# sensors.net
KiCad netlist of a schematic drawn in Altium Designer
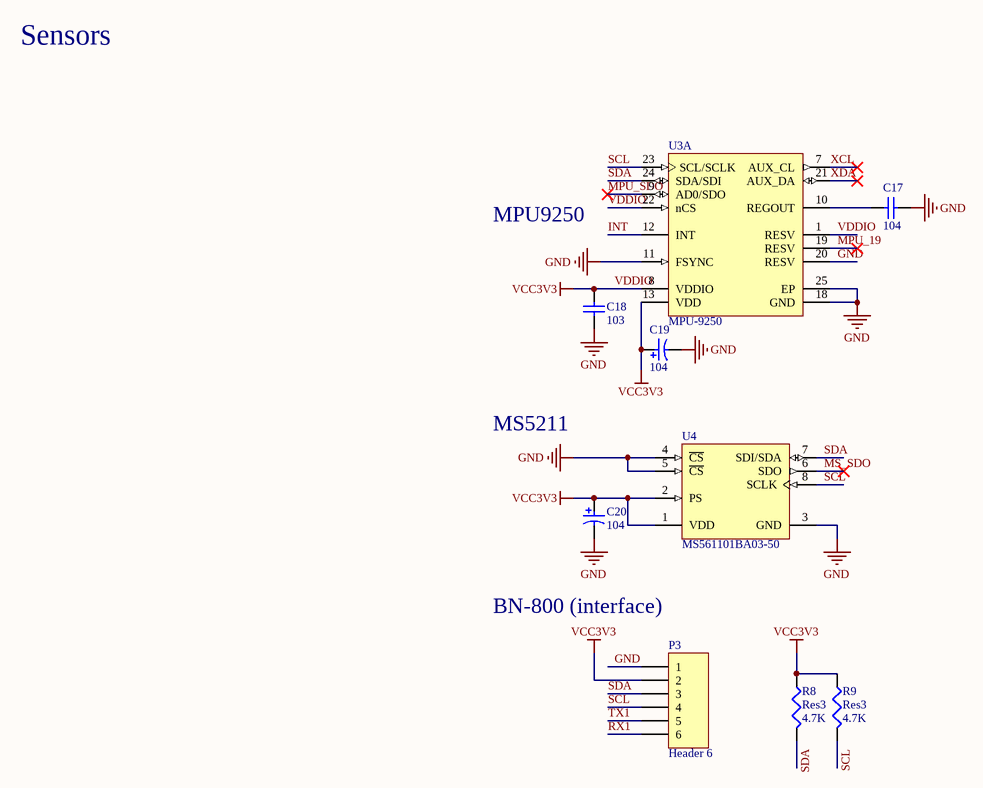
[diagram p0: sensors.SchDoc]

(export (version "E")
  (design (tool "Eeschema 10.0.6"))
  (components
    (comp (ref "C17")
      (value "104")
      (footprint "C 0603")
      (fields (field (name "PUBLISHER") "Altium Limited"))
      (libsource (lib "stm32原理图库") (part "Cap"))
    )
    (comp (ref "C18")
      (value "103")
      (footprint "C 0603")
      (fields (field (name "PUBLISHER") "Altium Limited"))
      (libsource (lib "stm32原理图库") (part "Cap"))
    )
    (comp (ref "C19")
      (value "104")
      (footprint "AVX-1206-2-H1.8_L")
      (fields
        (field (name "TOLERANCE") "±10%")
        (field (name "MANUFACTURER") "AVX")
        (field (name "PCN PART NUMBER") "TAJSeriesSuffix08/Dec/2008")
      )
      (libsource (lib "Altium Content Vault") (part "CAP-P-2"))
    )
    (comp (ref "C20")
      (value "104")
      (footprint "AVX-1206-2-H1.8_L")
      (fields
        (field (name "TOLERANCE") "±10%")
        (field (name "MANUFACTURER") "AVX")
        (field (name "PCN PART NUMBER") "TAJSeriesSuffix08/Dec/2008")
      )
      (libsource (lib "Altium Content Vault") (part "CAP-P-2"))
    )
    (comp (ref "P3")
      (value "Header 6")
      (footprint "HDR1X6")
      (description "Header, 6-Pin")
      (fields (field (name "PUBLISHER") "Altium Limited"))
      (libsource (lib "Miscellaneous Connectors") (part "Header 6"))
    )
    (comp (ref "R8")
      (value "Res3")
      (footprint "J1-0603")
      (description "Resistor")
      (fields (field (name "ALTIUM_VALUE") "4.7K") (field (name "PUBLISHER") "Altium Limited"))
      (libsource (lib "Miscellaneous Devices") (part "Res3"))
    )
    (comp (ref "R9")
      (value "Res3")
      (footprint "J1-0603")
      (description "Resistor")
      (fields (field (name "ALTIUM_VALUE") "4.7K") (field (name "PUBLISHER") "Altium Limited"))
      (libsource (lib "Miscellaneous Devices") (part "Res3"))
    )
    (comp (ref "U3")
      (value "MPU-9250")
      (footprint "INSE-QFN-24-1700X1540TP_M")
      (description "9-axis MotionTracking device, 2.4 to 3,6 V, -40 to 85 degC, 24-Pin QFN, RoHS, Tape and Reel")
      (fields (field (name "MANUFACTURER") "InvenSense"))
      (libsource (lib "Altium Content Vault") (part "INSE-MPU-9250-QFN-24"))
    )
    (comp (ref "U4")
      (value "MS561101BA03-50")
      (footprint "MSI-MS561101BA03-50-8_V")
      (fields (field (name "MANUFACTURER") "Measurement Specialties"))
      (libsource (lib "Altium Content Vault") (part "MSI-MS561101BA03-50-8"))
    )
  )
  (nets
    (net (code "1") (name "/INT") (class "Default")
      (node (ref "U3") (pin "12") (pinfunction "INT_12") (pintype "tri_state"))
    )
    (net (code "2") (name "/MPU_19") (class "Default")
      (node (ref "U3") (pin "19") (pinfunction "RESV_19") (pintype "passive+no_connect"))
    )
    (net (code "3") (name "/MPU_SDO") (class "Default")
      (node (ref "U3") (pin "9") (pinfunction "AD0/SDO_9") (pintype "bidirectional+no_connect"))
    )
    (net (code "4") (name "/MS_SDO") (class "Default")
      (node (ref "U4") (pin "6") (pinfunction "SDO_6") (pintype "output+no_connect"))
    )
    (net (code "5") (name "/RX1") (class "Default")
      (node (ref "P3") (pin "6") (pinfunction "6_6") (pintype "passive"))
    )
    (net (code "6") (name "/SCL") (class "Default")
      (node (ref "P3") (pin "4") (pinfunction "4_4") (pintype "passive"))
      (node (ref "R9") (pin "2") (pinfunction "2_2") (pintype "passive"))
      (node (ref "U3") (pin "23") (pinfunction "SCL/SCLK_23") (pintype "input"))
      (node (ref "U4") (pin "8") (pinfunction "SCLK_8") (pintype "input"))
    )
    (net (code "7") (name "/SDA") (class "Default")
      (node (ref "P3") (pin "3") (pinfunction "3_3") (pintype "passive"))
      (node (ref "R8") (pin "2") (pinfunction "2_2") (pintype "passive"))
      (node (ref "U3") (pin "24") (pinfunction "SDA/SDI_24") (pintype "bidirectional"))
      (node (ref "U4") (pin "7") (pinfunction "SDI/SDA_7") (pintype "bidirectional"))
    )
    (net (code "8") (name "/TX1") (class "Default")
      (node (ref "P3") (pin "5") (pinfunction "5_5") (pintype "passive"))
    )
    (net (code "9") (name "/XCL") (class "Default")
      (node (ref "U3") (pin "7") (pinfunction "AUX_CL_7") (pintype "output+no_connect"))
    )
    (net (code "10") (name "/XDA") (class "Default")
      (node (ref "U3") (pin "21") (pinfunction "AUX_DA_21") (pintype "bidirectional+no_connect"))
    )
    (net (code "11") (name "GND") (class "Default")
      (node (ref "C17") (pin "1") (pinfunction "1_1") (pintype "passive"))
      (node (ref "C18") (pin "1") (pinfunction "1_1") (pintype "passive"))
      (node (ref "C19") (pin "2") (pinfunction "2_2") (pintype "passive"))
      (node (ref "C20") (pin "2") (pinfunction "2_2") (pintype "passive"))
      (node (ref "P3") (pin "1") (pinfunction "1_1") (pintype "passive"))
      (node (ref "U3") (pin "11") (pinfunction "FSYNC_11") (pintype "input"))
      (node (ref "U3") (pin "18") (pinfunction "GND_18") (pintype "power_in"))
      (node (ref "U3") (pin "20") (pinfunction "RESV_20") (pintype "power_in"))
      (node (ref "U3") (pin "25") (pinfunction "EP_25") (pintype "passive"))
      (node (ref "U4") (pin "3") (pinfunction "GND_3") (pintype "power_in"))
      (node (ref "U4") (pin "4") (pinfunction "~{CS}_4") (pintype "input"))
      (node (ref "U4") (pin "5") (pinfunction "~{CS}_5") (pintype "input"))
    )
    (net (code "12") (name "Net-(U3A-REGOUT)") (class "Default")
      (node (ref "C17") (pin "2") (pinfunction "2_2") (pintype "passive"))
      (node (ref "U3") (pin "10") (pinfunction "REGOUT_10") (pintype "passive"))
    )
    (net (code "13") (name "VCC3V3") (class "Default")
      (node (ref "C18") (pin "2") (pinfunction "2_2") (pintype "passive"))
      (node (ref "C19") (pin "1") (pinfunction "1_1") (pintype "passive"))
      (node (ref "C20") (pin "1") (pinfunction "1_1") (pintype "passive"))
      (node (ref "P3") (pin "2") (pinfunction "2_2") (pintype "passive"))
      (node (ref "R8") (pin "1") (pinfunction "1_1") (pintype "passive"))
      (node (ref "R9") (pin "1") (pinfunction "1_1") (pintype "passive"))
      (node (ref "U3") (pin "1") (pinfunction "RESV_1") (pintype "power_in"))
      (node (ref "U3") (pin "13") (pinfunction "VDD_13") (pintype "power_in"))
      (node (ref "U3") (pin "22") (pinfunction "nCS_22") (pintype "input"))
      (node (ref "U3") (pin "8") (pinfunction "VDDIO_8") (pintype "power_in"))
      (node (ref "U4") (pin "1") (pinfunction "VDD_1") (pintype "power_in"))
      (node (ref "U4") (pin "2") (pinfunction "PS_2") (pintype "input"))
    )
  )
)
